# Button_connections.net
KiCad netlist of a schematic drawn in Altium Designer
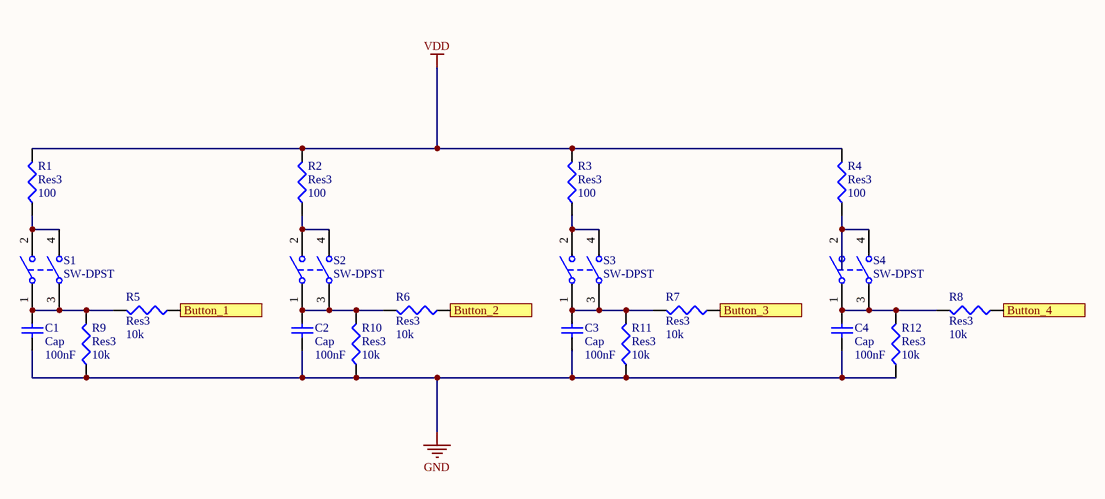
[diagram p0: Button_connections.SchDoc]

(export (version "E")
  (design (tool "Eeschema 10.0.6"))
  (components
    (comp (ref "C1")
      (value "Cap")
      (footprint "C0805")
      (description "Capacitor")
      (fields (field (name "ALTIUM_VALUE") "100nF") (field (name "PUBLISHER") "Altium Limited"))
      (libsource (lib "Miscellaneous Devices") (part "Cap"))
    )
    (comp (ref "C2")
      (value "Cap")
      (footprint "C0805")
      (description "Capacitor")
      (fields (field (name "ALTIUM_VALUE") "100nF") (field (name "PUBLISHER") "Altium Limited"))
      (libsource (lib "Miscellaneous Devices") (part "Cap"))
    )
    (comp (ref "C3")
      (value "Cap")
      (footprint "C0805")
      (description "Capacitor")
      (fields (field (name "ALTIUM_VALUE") "100nF") (field (name "PUBLISHER") "Altium Limited"))
      (libsource (lib "Miscellaneous Devices") (part "Cap"))
    )
    (comp (ref "C4")
      (value "Cap")
      (footprint "C0805")
      (description "Capacitor")
      (fields (field (name "ALTIUM_VALUE") "100nF") (field (name "PUBLISHER") "Altium Limited"))
      (libsource (lib "Miscellaneous Devices") (part "Cap"))
    )
    (comp (ref "R1")
      (value "Res3")
      (footprint "1608[0603]")
      (description "Resistor")
      (fields (field (name "ALTIUM_VALUE") "100") (field (name "PUBLISHER") "Altium Limited"))
      (libsource (lib "Miscellaneous Devices") (part "Res3"))
    )
    (comp (ref "R2")
      (value "Res3")
      (footprint "1608[0603]")
      (description "Resistor")
      (fields (field (name "ALTIUM_VALUE") "100") (field (name "PUBLISHER") "Altium Limited"))
      (libsource (lib "Miscellaneous Devices") (part "Res3"))
    )
    (comp (ref "R3")
      (value "Res3")
      (footprint "1608[0603]")
      (description "Resistor")
      (fields (field (name "ALTIUM_VALUE") "100") (field (name "PUBLISHER") "Altium Limited"))
      (libsource (lib "Miscellaneous Devices") (part "Res3"))
    )
    (comp (ref "R4")
      (value "Res3")
      (footprint "1608[0603]")
      (description "Resistor")
      (fields (field (name "ALTIUM_VALUE") "100") (field (name "PUBLISHER") "Altium Limited"))
      (libsource (lib "Miscellaneous Devices") (part "Res3"))
    )
    (comp (ref "R5")
      (value "Res3")
      (footprint "1608[0603]")
      (description "Resistor")
      (fields (field (name "ALTIUM_VALUE") "10k") (field (name "PUBLISHER") "Altium Limited"))
      (libsource (lib "Miscellaneous Devices") (part "Res3"))
    )
    (comp (ref "R6")
      (value "Res3")
      (footprint "1608[0603]")
      (description "Resistor")
      (fields (field (name "ALTIUM_VALUE") "10k") (field (name "PUBLISHER") "Altium Limited"))
      (libsource (lib "Miscellaneous Devices") (part "Res3"))
    )
    (comp (ref "R7")
      (value "Res3")
      (footprint "1608[0603]")
      (description "Resistor")
      (fields (field (name "ALTIUM_VALUE") "10k") (field (name "PUBLISHER") "Altium Limited"))
      (libsource (lib "Miscellaneous Devices") (part "Res3"))
    )
    (comp (ref "R8")
      (value "Res3")
      (footprint "1608[0603]")
      (description "Resistor")
      (fields (field (name "ALTIUM_VALUE") "10k") (field (name "PUBLISHER") "Altium Limited"))
      (libsource (lib "Miscellaneous Devices") (part "Res3"))
    )
    (comp (ref "R9")
      (value "Res3")
      (footprint "1608[0603]")
      (description "Resistor")
      (fields (field (name "ALTIUM_VALUE") "10k") (field (name "PUBLISHER") "Altium Limited"))
      (libsource (lib "Miscellaneous Devices") (part "Res3"))
    )
    (comp (ref "R10")
      (value "Res3")
      (footprint "1608[0603]")
      (description "Resistor")
      (fields (field (name "ALTIUM_VALUE") "10k") (field (name "PUBLISHER") "Altium Limited"))
      (libsource (lib "Miscellaneous Devices") (part "Res3"))
    )
    (comp (ref "R11")
      (value "Res3")
      (footprint "1608[0603]")
      (description "Resistor")
      (fields (field (name "ALTIUM_VALUE") "10k") (field (name "PUBLISHER") "Altium Limited"))
      (libsource (lib "Miscellaneous Devices") (part "Res3"))
    )
    (comp (ref "R12")
      (value "Res3")
      (footprint "1608[0603]")
      (description "Resistor")
      (fields (field (name "ALTIUM_VALUE") "10k") (field (name "PUBLISHER") "Altium Limited"))
      (libsource (lib "Miscellaneous Devices") (part "Res3"))
    )
    (comp (ref "S1")
      (value "SW-DPST")
      (footprint "PCBComponent_1")
      (description "Double-Pole, Single-Throw Switch")
      (fields (field (name "PUBLISHER") "Altium Limited"))
      (libsource (lib "Miscellaneous Devices") (part "SW-DPST"))
    )
    (comp (ref "S2")
      (value "SW-DPST")
      (footprint "PCBComponent_1")
      (description "Double-Pole, Single-Throw Switch")
      (fields (field (name "PUBLISHER") "Altium Limited"))
      (libsource (lib "Miscellaneous Devices") (part "SW-DPST"))
    )
    (comp (ref "S3")
      (value "SW-DPST")
      (footprint "PCBComponent_1")
      (description "Double-Pole, Single-Throw Switch")
      (fields (field (name "PUBLISHER") "Altium Limited"))
      (libsource (lib "Miscellaneous Devices") (part "SW-DPST"))
    )
    (comp (ref "S4")
      (value "SW-DPST")
      (footprint "PCBComponent_1")
      (description "Double-Pole, Single-Throw Switch")
      (fields (field (name "PUBLISHER") "Altium Limited"))
      (libsource (lib "Miscellaneous Devices") (part "SW-DPST"))
    )
  )
  (nets
    (net (code "1") (name "/Button_1") (class "Default")
      (node (ref "R5") (pin "1") (pinfunction "1_1") (pintype "passive"))
    )
    (net (code "2") (name "/Button_2") (class "Default")
      (node (ref "R6") (pin "1") (pinfunction "1_1") (pintype "passive"))
    )
    (net (code "3") (name "/Button_3") (class "Default")
      (node (ref "R7") (pin "1") (pinfunction "1_1") (pintype "passive"))
    )
    (net (code "4") (name "/Button_4") (class "Default")
      (node (ref "R8") (pin "1") (pinfunction "1_1") (pintype "passive"))
    )
    (net (code "5") (name "GND") (class "Default")
      (node (ref "C1") (pin "1") (pinfunction "1_1") (pintype "passive"))
      (node (ref "C2") (pin "1") (pinfunction "1_1") (pintype "passive"))
      (node (ref "C3") (pin "1") (pinfunction "1_1") (pintype "passive"))
      (node (ref "C4") (pin "1") (pinfunction "1_1") (pintype "passive"))
      (node (ref "R10") (pin "1") (pinfunction "1_1") (pintype "passive"))
      (node (ref "R11") (pin "1") (pinfunction "1_1") (pintype "passive"))
      (node (ref "R12") (pin "1") (pinfunction "1_1") (pintype "passive"))
      (node (ref "R9") (pin "1") (pinfunction "1_1") (pintype "passive"))
    )
    (net (code "6") (name "Net-(S1-COMMON1)") (class "Default")
      (node (ref "C1") (pin "2") (pinfunction "2_2") (pintype "passive"))
      (node (ref "R5") (pin "2") (pinfunction "2_2") (pintype "passive"))
      (node (ref "R9") (pin "2") (pinfunction "2_2") (pintype "passive"))
      (node (ref "S1") (pin "1") (pinfunction "COMMON1_1") (pintype "passive"))
      (node (ref "S1") (pin "3") (pinfunction "COMMON2_3") (pintype "passive"))
    )
    (net (code "7") (name "Net-(S1-NO1)") (class "Default")
      (node (ref "R1") (pin "1") (pinfunction "1_1") (pintype "passive"))
      (node (ref "S1") (pin "2") (pinfunction "NO1_2") (pintype "passive"))
      (node (ref "S1") (pin "4") (pinfunction "NO2_4") (pintype "passive"))
    )
    (net (code "8") (name "Net-(S2-COMMON1)") (class "Default")
      (node (ref "C2") (pin "2") (pinfunction "2_2") (pintype "passive"))
      (node (ref "R10") (pin "2") (pinfunction "2_2") (pintype "passive"))
      (node (ref "R6") (pin "2") (pinfunction "2_2") (pintype "passive"))
      (node (ref "S2") (pin "1") (pinfunction "COMMON1_1") (pintype "passive"))
      (node (ref "S2") (pin "3") (pinfunction "COMMON2_3") (pintype "passive"))
    )
    (net (code "9") (name "Net-(S2-NO1)") (class "Default")
      (node (ref "R2") (pin "1") (pinfunction "1_1") (pintype "passive"))
      (node (ref "S2") (pin "2") (pinfunction "NO1_2") (pintype "passive"))
      (node (ref "S2") (pin "4") (pinfunction "NO2_4") (pintype "passive"))
    )
    (net (code "10") (name "Net-(S3-COMMON1)") (class "Default")
      (node (ref "C3") (pin "2") (pinfunction "2_2") (pintype "passive"))
      (node (ref "R11") (pin "2") (pinfunction "2_2") (pintype "passive"))
      (node (ref "R7") (pin "2") (pinfunction "2_2") (pintype "passive"))
      (node (ref "S3") (pin "1") (pinfunction "COMMON1_1") (pintype "passive"))
      (node (ref "S3") (pin "3") (pinfunction "COMMON2_3") (pintype "passive"))
    )
    (net (code "11") (name "Net-(S3-NO1)") (class "Default")
      (node (ref "R3") (pin "1") (pinfunction "1_1") (pintype "passive"))
      (node (ref "S3") (pin "2") (pinfunction "NO1_2") (pintype "passive"))
      (node (ref "S3") (pin "4") (pinfunction "NO2_4") (pintype "passive"))
    )
    (net (code "12") (name "Net-(S4-COMMON1)") (class "Default")
      (node (ref "C4") (pin "2") (pinfunction "2_2") (pintype "passive"))
      (node (ref "R12") (pin "2") (pinfunction "2_2") (pintype "passive"))
      (node (ref "R8") (pin "2") (pinfunction "2_2") (pintype "passive"))
      (node (ref "S4") (pin "1") (pinfunction "COMMON1_1") (pintype "passive"))
      (node (ref "S4") (pin "3") (pinfunction "COMMON2_3") (pintype "passive"))
    )
    (net (code "13") (name "Net-(S4-NO1)") (class "Default")
      (node (ref "R4") (pin "1") (pinfunction "1_1") (pintype "passive"))
      (node (ref "S4") (pin "2") (pinfunction "NO1_2") (pintype "passive"))
      (node (ref "S4") (pin "4") (pinfunction "NO2_4") (pintype "passive"))
    )
    (net (code "14") (name "VDD") (class "Default")
      (node (ref "R1") (pin "2") (pinfunction "2_2") (pintype "passive"))
      (node (ref "R2") (pin "2") (pinfunction "2_2") (pintype "passive"))
      (node (ref "R3") (pin "2") (pinfunction "2_2") (pintype "passive"))
      (node (ref "R4") (pin "2") (pinfunction "2_2") (pintype "passive"))
    )
  )
)
